# Apo_Board_2017.net
KiCad netlist of a schematic drawn in EAGLE
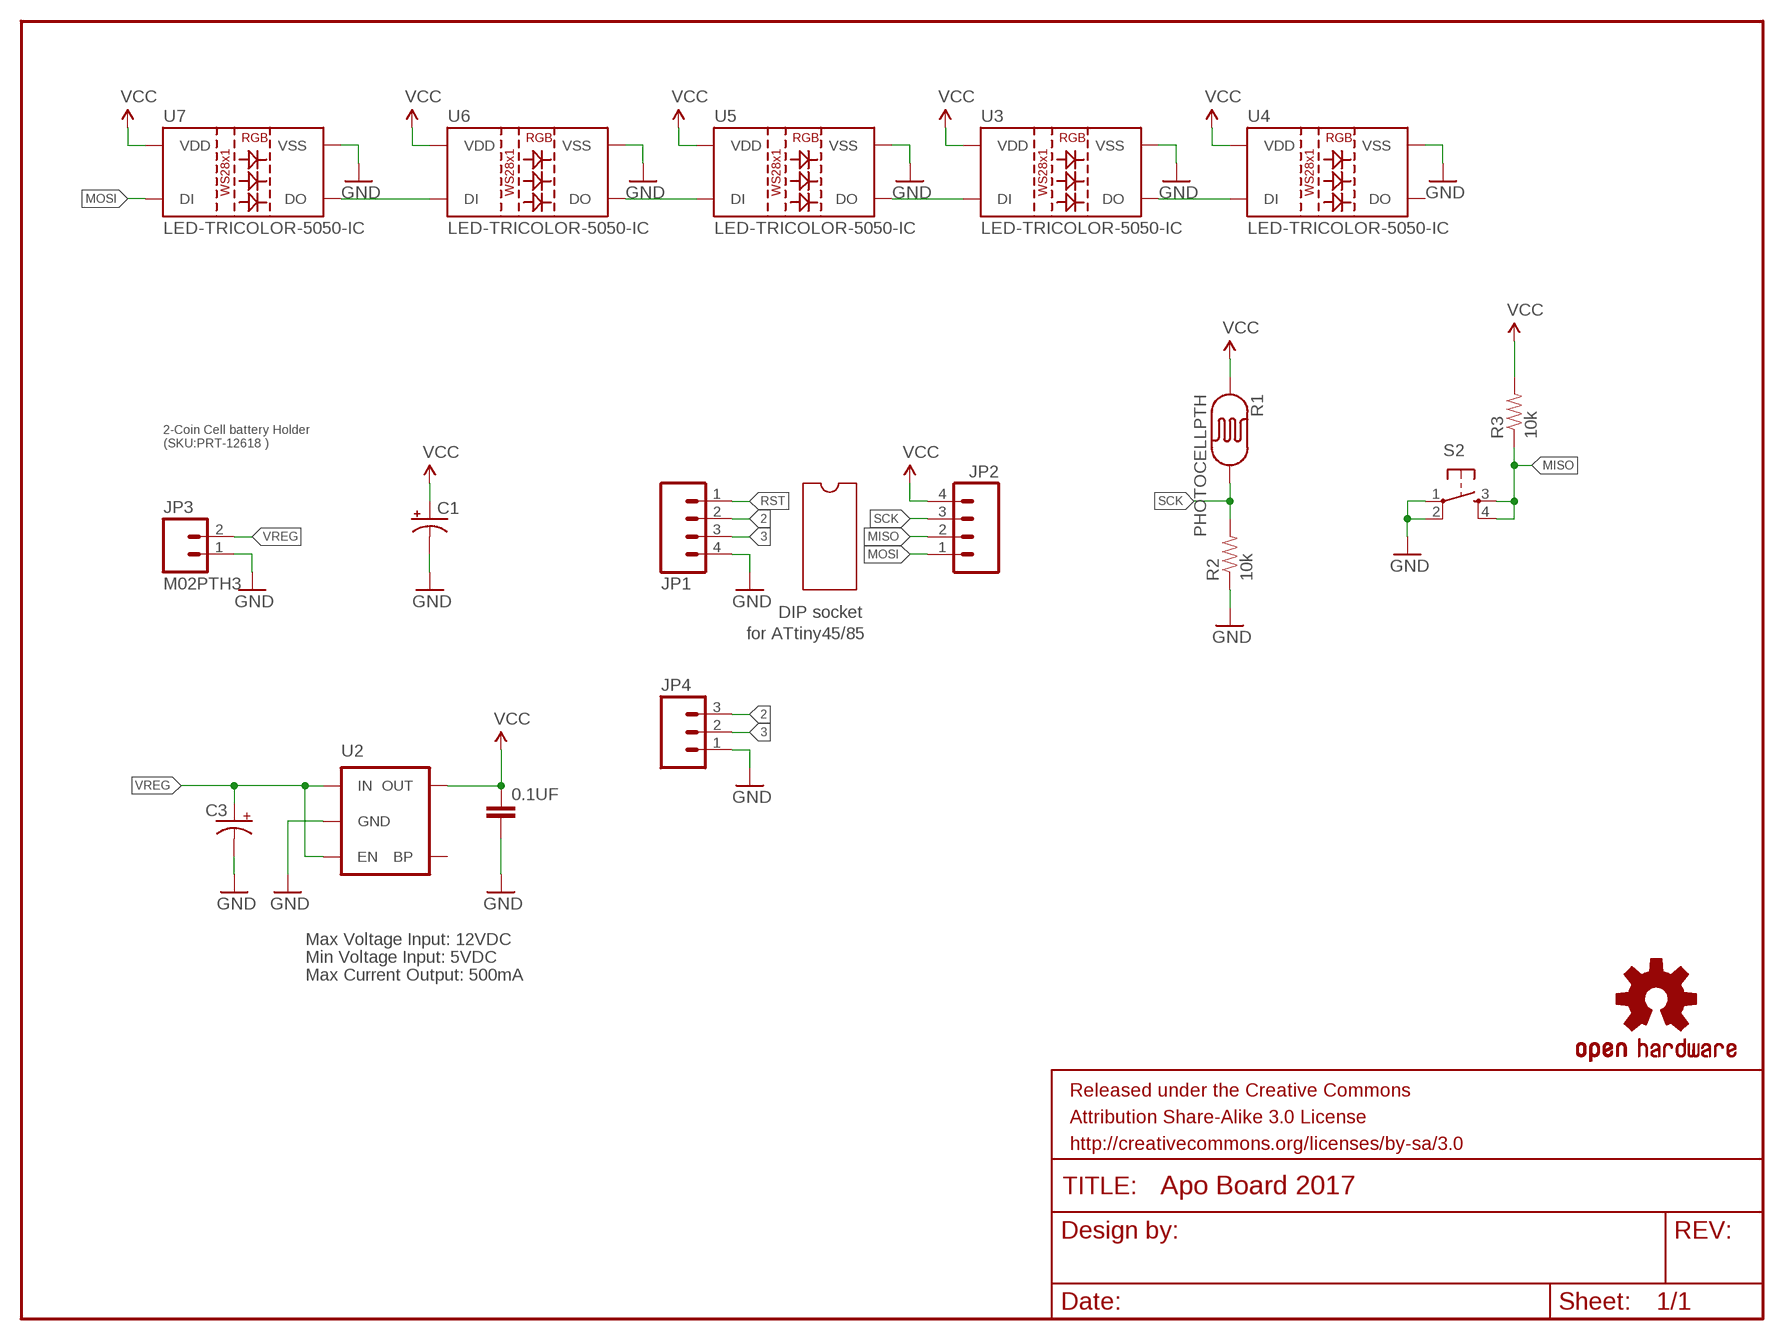
[diagram p0: schematic, sheet 1]

(export (version "E")
  (design (tool "Eeschema 10.0.6"))
  (components
    (comp (ref "0.1UF")
      (value "CAPKIT")
      (footprint "eagle-import:CAP-PTH-SMALL-KIT")
      (libsource (lib "eagle-import") (part "CAPKIT"))
    )
    (comp (ref "C1")
      (value "CAP_POLPTH2")
      (footprint "eagle-import:CPOL-RADIAL-10UF-25V")
      (libsource (lib "eagle-import") (part "CAP_POLPTH2"))
    )
    (comp (ref "C3")
      (value "CAP_POLPTH2")
      (footprint "eagle-import:CPOL-RADIAL-10UF-25V")
      (libsource (lib "eagle-import") (part "CAP_POLPTH2"))
    )
    (comp (ref "FRAME1")
      (value "FRAME-LETTER")
      (footprint "eagle-import:CREATIVE_COMMONS")
      (libsource (lib "eagle-import") (part "FRAME-LETTER"))
    )
    (comp (ref "JP1")
      (value "M04PTH")
      (footprint "eagle-import:1X04")
      (libsource (lib "eagle-import") (part "M04PTH"))
    )
    (comp (ref "JP2")
      (value "M04PTH")
      (footprint "eagle-import:1X04")
      (libsource (lib "eagle-import") (part "M04PTH"))
    )
    (comp (ref "JP3")
      (value "M02PTH3")
      (footprint "eagle-import:1X02_LONGPADS")
      (libsource (lib "eagle-import") (part "M02PTH3"))
    )
    (comp (ref "JP4")
      (value "M031X03_NO_SILK")
      (footprint "eagle-import:1X03_NO_SILK")
      (libsource (lib "eagle-import") (part "M031X03_NO_SILK"))
    )
    (comp (ref "LOGO1")
      (value "OSHW-LOGOS")
      (footprint "eagle-import:OSHW-LOGO-S")
      (libsource (lib "eagle-import") (part "OSHW-LOGOS"))
    )
    (comp (ref "R1")
      (value "PHOTOCELLPTH")
      (footprint "eagle-import:PHOTOCELL")
      (libsource (lib "eagle-import") (part "PHOTOCELLPTH"))
    )
    (comp (ref "R2")
      (value "10k")
      (footprint "eagle-import:AXIAL-0.4")
      (libsource (lib "eagle-import") (part "RESISTORPTH-1/4W"))
    )
    (comp (ref "R3")
      (value "10k")
      (footprint "eagle-import:AXIAL-0.4")
      (libsource (lib "eagle-import") (part "RESISTORPTH-1/4W"))
    )
    (comp (ref "S2")
      (value "TAC_SWITCHPTH")
      (footprint "eagle-import:TACTILE-PTH")
      (libsource (lib "eagle-import") (part "TAC_SWITCHPTH"))
    )
    (comp (ref "U2")
      (value "MIC52055V")
      (footprint "eagle-import:SOT23-5")
      (libsource (lib "eagle-import") (part "MIC52055V"))
    )
    (comp (ref "U3")
      (value "LED-TRICOLOR-5050-IC")
      (footprint "eagle-import:LED-RGB-THRU")
      (libsource (lib "eagle-import") (part "LED-TRICOLOR-5050-IC"))
    )
    (comp (ref "U4")
      (value "LED-TRICOLOR-5050-IC")
      (footprint "eagle-import:LED-RGB-THRU")
      (libsource (lib "eagle-import") (part "LED-TRICOLOR-5050-IC"))
    )
    (comp (ref "U5")
      (value "LED-TRICOLOR-5050-IC")
      (footprint "eagle-import:LED-RGB-THRU")
      (libsource (lib "eagle-import") (part "LED-TRICOLOR-5050-IC"))
    )
    (comp (ref "U6")
      (value "LED-TRICOLOR-5050-IC")
      (footprint "eagle-import:LED-RGB-THRU")
      (libsource (lib "eagle-import") (part "LED-TRICOLOR-5050-IC"))
    )
    (comp (ref "U7")
      (value "LED-TRICOLOR-5050-IC")
      (footprint "eagle-import:LED-RGB-THRU")
      (libsource (lib "eagle-import") (part "LED-TRICOLOR-5050-IC"))
    )
  )
  (nets
    (net (code "1") (name "2") (class "Default")
      (node (ref "JP1") (pin "2") (pinfunction "2_2") (pintype "passive"))
      (node (ref "JP4") (pin "3") (pinfunction "3_3") (pintype "passive"))
    )
    (net (code "2") (name "3") (class "Default")
      (node (ref "JP1") (pin "3") (pinfunction "3_3") (pintype "passive"))
      (node (ref "JP4") (pin "2") (pinfunction "2_2") (pintype "passive"))
    )
    (net (code "3") (name "GND") (class "Default")
      (node (ref "0.1UF") (pin "2") (pinfunction "2_2") (pintype "passive"))
      (node (ref "C1") (pin "2") (pinfunction "-_2") (pintype "passive"))
      (node (ref "C3") (pin "2") (pinfunction "-_2") (pintype "passive"))
      (node (ref "JP1") (pin "4") (pinfunction "4_4") (pintype "passive"))
      (node (ref "JP3") (pin "1") (pinfunction "1_1") (pintype "passive"))
      (node (ref "JP4") (pin "1") (pinfunction "1_1") (pintype "passive"))
      (node (ref "R2") (pin "P$1") (pinfunction "1_P$1") (pintype "passive"))
      (node (ref "S2") (pin "1") (pinfunction "1_1") (pintype "passive"))
      (node (ref "S2") (pin "2") (pinfunction "2_2") (pintype "passive"))
      (node (ref "U2") (pin "2") (pinfunction "GND_2") (pintype "input"))
      (node (ref "U3") (pin "3") (pinfunction "VSS_3") (pintype "bidirectional"))
      (node (ref "U4") (pin "3") (pinfunction "VSS_3") (pintype "bidirectional"))
      (node (ref "U5") (pin "3") (pinfunction "VSS_3") (pintype "bidirectional"))
      (node (ref "U6") (pin "3") (pinfunction "VSS_3") (pintype "bidirectional"))
      (node (ref "U7") (pin "3") (pinfunction "VSS_3") (pintype "bidirectional"))
    )
    (net (code "4") (name "MISO") (class "Default")
      (node (ref "JP2") (pin "2") (pinfunction "2_2") (pintype "passive"))
      (node (ref "R3") (pin "P$1") (pinfunction "1_P$1") (pintype "passive"))
      (node (ref "S2") (pin "3") (pinfunction "3_3") (pintype "passive"))
      (node (ref "S2") (pin "4") (pinfunction "4_4") (pintype "passive"))
    )
    (net (code "5") (name "MOSI") (class "Default")
      (node (ref "JP2") (pin "1") (pinfunction "1_1") (pintype "passive"))
      (node (ref "U7") (pin "1") (pinfunction "DI_1") (pintype "bidirectional"))
    )
    (net (code "6") (name "Net-(U3-DI)") (class "Default")
      (node (ref "U3") (pin "1") (pinfunction "DI_1") (pintype "bidirectional"))
      (node (ref "U5") (pin "4") (pinfunction "DO_4") (pintype "bidirectional"))
    )
    (net (code "7") (name "Net-(U3-DO)") (class "Default")
      (node (ref "U3") (pin "4") (pinfunction "DO_4") (pintype "bidirectional"))
      (node (ref "U4") (pin "1") (pinfunction "DI_1") (pintype "bidirectional"))
    )
    (net (code "8") (name "Net-(U5-DI)") (class "Default")
      (node (ref "U5") (pin "1") (pinfunction "DI_1") (pintype "bidirectional"))
      (node (ref "U6") (pin "4") (pinfunction "DO_4") (pintype "bidirectional"))
    )
    (net (code "9") (name "Net-(U6-DI)") (class "Default")
      (node (ref "U6") (pin "1") (pinfunction "DI_1") (pintype "bidirectional"))
      (node (ref "U7") (pin "4") (pinfunction "DO_4") (pintype "bidirectional"))
    )
    (net (code "10") (name "RST") (class "Default")
      (node (ref "JP1") (pin "1") (pinfunction "1_1") (pintype "passive"))
    )
    (net (code "11") (name "SCK") (class "Default")
      (node (ref "JP2") (pin "3") (pinfunction "3_3") (pintype "passive"))
      (node (ref "R1") (pin "2") (pinfunction "P$2_2") (pintype "bidirectional"))
      (node (ref "R2") (pin "P$2") (pinfunction "2_P$2") (pintype "passive"))
    )
    (net (code "12") (name "VCC") (class "Default")
      (node (ref "0.1UF") (pin "1") (pinfunction "1_1") (pintype "passive"))
      (node (ref "C1") (pin "1") (pinfunction "+_1") (pintype "passive"))
      (node (ref "JP2") (pin "4") (pinfunction "4_4") (pintype "passive"))
      (node (ref "R1") (pin "1") (pinfunction "P$1_1") (pintype "bidirectional"))
      (node (ref "R3") (pin "P$2") (pinfunction "2_P$2") (pintype "passive"))
      (node (ref "U2") (pin "5") (pinfunction "OUT_5") (pintype "passive"))
      (node (ref "U3") (pin "2") (pinfunction "VDD_2") (pintype "bidirectional"))
      (node (ref "U4") (pin "2") (pinfunction "VDD_2") (pintype "bidirectional"))
      (node (ref "U5") (pin "2") (pinfunction "VDD_2") (pintype "bidirectional"))
      (node (ref "U6") (pin "2") (pinfunction "VDD_2") (pintype "bidirectional"))
      (node (ref "U7") (pin "2") (pinfunction "VDD_2") (pintype "bidirectional"))
    )
    (net (code "13") (name "VREG") (class "Default")
      (node (ref "C3") (pin "1") (pinfunction "+_1") (pintype "passive"))
      (node (ref "JP3") (pin "2") (pinfunction "2_2") (pintype "passive"))
      (node (ref "U2") (pin "1") (pinfunction "IN_1") (pintype "input"))
      (node (ref "U2") (pin "3") (pinfunction "EN_3") (pintype "input"))
    )
    (net (code "14") (name "unconnected-(U2-BP-Pad4)") (class "Default")
      (node (ref "U2") (pin "4") (pinfunction "BP_4") (pintype "input"))
    )
    (net (code "15") (name "unconnected-(U4-DO-Pad4)") (class "Default")
      (node (ref "U4") (pin "4") (pinfunction "DO_4") (pintype "bidirectional"))
    )
  )
)
